# bat_connectors.net
KiCad netlist of a schematic drawn in Altium Designer
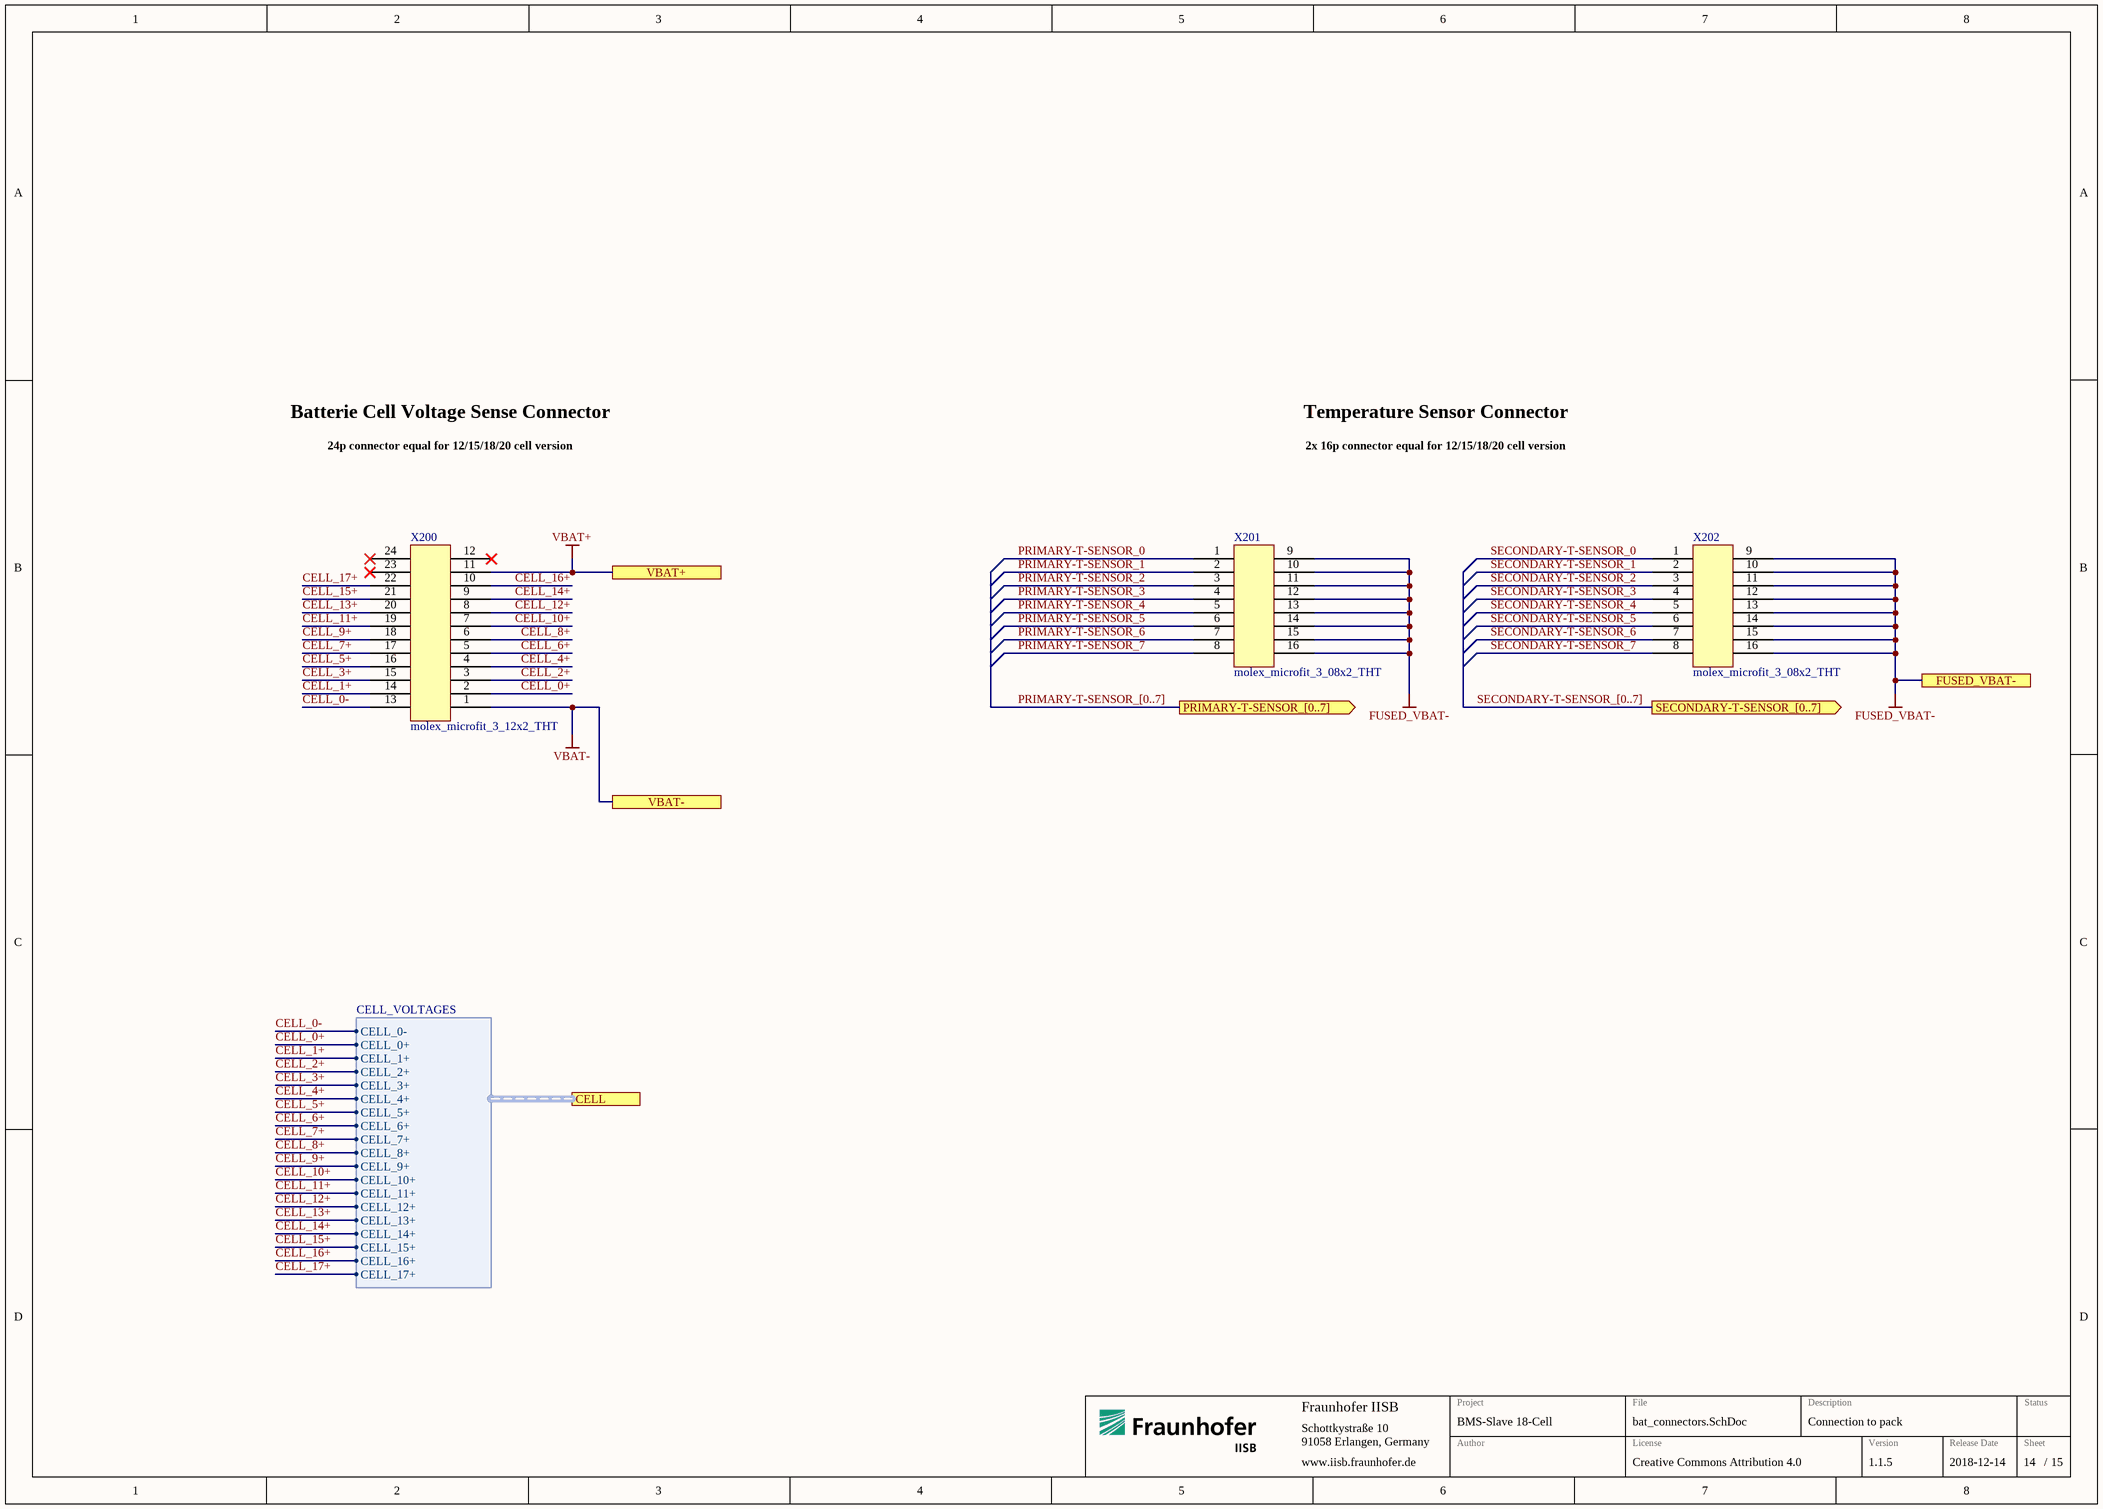
[diagram p0: bat_connectors.SchDoc]

(export (version "E")
  (design (tool "Eeschema 10.0.6"))
  (components
    (comp (ref "X200")
      (value "molex_microfit_3_12x2_THT")
      (footprint "MOLEX_MICROFIT_12x2_THT")
      (fields (field (name "MANUFACTURER") "Molex"))
      (libsource (lib "OE750") (part "X12x2"))
    )
    (comp (ref "X201")
      (value "molex_microfit_3_08x2_THT")
      (footprint "MOLEX_MICROFIT_08x2_THT")
      (fields (field (name "MANUFACTURER") "Molex"))
      (libsource (lib "OE750") (part "X8x2"))
    )
    (comp (ref "X202")
      (value "molex_microfit_3_08x2_THT")
      (footprint "MOLEX_MICROFIT_08x2_THT")
      (fields (field (name "MANUFACTURER") "Molex"))
      (libsource (lib "OE750") (part "X8x2"))
    )
  )
  (nets
    (net (code "2") (name "/CELL_0+") (class "Default") (node (ref "X200") (pin "2") (pintype "passive")))
    (net (code "3") (name "/CELL_0-") (class "Default") (node (ref "X200") (pin "13") (pintype "passive")))
    (net (code "4") (name "/CELL_1+") (class "Default") (node (ref "X200") (pin "14") (pintype "passive")))
    (net (code "5") (name "/CELL_2+") (class "Default") (node (ref "X200") (pin "3") (pintype "passive")))
    (net (code "6") (name "/CELL_3+") (class "Default") (node (ref "X200") (pin "15") (pintype "passive")))
    (net (code "7") (name "/CELL_4+") (class "Default") (node (ref "X200") (pin "4") (pintype "passive")))
    (net (code "8") (name "/CELL_5+") (class "Default") (node (ref "X200") (pin "16") (pintype "passive")))
    (net (code "9") (name "/CELL_6+") (class "Default") (node (ref "X200") (pin "5") (pintype "passive")))
    (net (code "10") (name "/CELL_7+") (class "Default") (node (ref "X200") (pin "17") (pintype "passive")))
    (net (code "11") (name "/CELL_8+") (class "Default") (node (ref "X200") (pin "6") (pintype "passive")))
    (net (code "12") (name "/CELL_9+") (class "Default") (node (ref "X200") (pin "18") (pintype "passive")))
    (net (code "13") (name "/CELL_10+") (class "Default") (node (ref "X200") (pin "7") (pintype "passive")))
    (net (code "14") (name "/CELL_11+") (class "Default") (node (ref "X200") (pin "19") (pintype "passive")))
    (net (code "15") (name "/CELL_12+") (class "Default") (node (ref "X200") (pin "8") (pintype "passive")))
    (net (code "16") (name "/CELL_13+") (class "Default") (node (ref "X200") (pin "20") (pintype "passive")))
    (net (code "17") (name "/CELL_14+") (class "Default") (node (ref "X200") (pin "9") (pintype "passive")))
    (net (code "18") (name "/CELL_15+") (class "Default") (node (ref "X200") (pin "21") (pintype "passive")))
    (net (code "19") (name "/CELL_16+") (class "Default") (node (ref "X200") (pin "10") (pintype "passive")))
    (net (code "20") (name "/CELL_17+") (class "Default") (node (ref "X200") (pin "22") (pintype "passive")))
    (net (code "21") (name "/PRIMARY-T-SENSOR_0") (class "Default")
      (node (ref "X201") (pin "1") (pintype "passive"))
    )
    (net (code "22") (name "/PRIMARY-T-SENSOR_1") (class "Default")
      (node (ref "X201") (pin "2") (pintype "passive"))
    )
    (net (code "23") (name "/PRIMARY-T-SENSOR_2") (class "Default")
      (node (ref "X201") (pin "3") (pintype "passive"))
    )
    (net (code "24") (name "/PRIMARY-T-SENSOR_3") (class "Default")
      (node (ref "X201") (pin "4") (pintype "passive"))
    )
    (net (code "25") (name "/PRIMARY-T-SENSOR_4") (class "Default")
      (node (ref "X201") (pin "5") (pintype "passive"))
    )
    (net (code "26") (name "/PRIMARY-T-SENSOR_5") (class "Default")
      (node (ref "X201") (pin "6") (pintype "passive"))
    )
    (net (code "27") (name "/PRIMARY-T-SENSOR_6") (class "Default")
      (node (ref "X201") (pin "7") (pintype "passive"))
    )
    (net (code "28") (name "/PRIMARY-T-SENSOR_7") (class "Default")
      (node (ref "X201") (pin "8") (pintype "passive"))
    )
    (net (code "30") (name "/SECONDARY-T-SENSOR_0") (class "Default")
      (node (ref "X202") (pin "1") (pintype "passive"))
    )
    (net (code "31") (name "/SECONDARY-T-SENSOR_1") (class "Default")
      (node (ref "X202") (pin "2") (pintype "passive"))
    )
    (net (code "32") (name "/SECONDARY-T-SENSOR_2") (class "Default")
      (node (ref "X202") (pin "3") (pintype "passive"))
    )
    (net (code "33") (name "/SECONDARY-T-SENSOR_3") (class "Default")
      (node (ref "X202") (pin "4") (pintype "passive"))
    )
    (net (code "34") (name "/SECONDARY-T-SENSOR_4") (class "Default")
      (node (ref "X202") (pin "5") (pintype "passive"))
    )
    (net (code "35") (name "/SECONDARY-T-SENSOR_5") (class "Default")
      (node (ref "X202") (pin "6") (pintype "passive"))
    )
    (net (code "36") (name "/SECONDARY-T-SENSOR_6") (class "Default")
      (node (ref "X202") (pin "7") (pintype "passive"))
    )
    (net (code "37") (name "/SECONDARY-T-SENSOR_7") (class "Default")
      (node (ref "X202") (pin "8") (pintype "passive"))
    )
    (net (code "40") (name "FUSED_VBAT-") (class "Default")
      (node (ref "X201") (pin "10") (pintype "passive"))
      (node (ref "X201") (pin "11") (pintype "passive"))
      (node (ref "X201") (pin "12") (pintype "passive"))
      (node (ref "X201") (pin "13") (pintype "passive"))
      (node (ref "X201") (pin "14") (pintype "passive"))
      (node (ref "X201") (pin "15") (pintype "passive"))
      (node (ref "X201") (pin "16") (pintype "passive"))
      (node (ref "X201") (pin "9") (pintype "passive"))
      (node (ref "X202") (pin "10") (pintype "passive"))
      (node (ref "X202") (pin "11") (pintype "passive"))
      (node (ref "X202") (pin "12") (pintype "passive"))
      (node (ref "X202") (pin "13") (pintype "passive"))
      (node (ref "X202") (pin "14") (pintype "passive"))
      (node (ref "X202") (pin "15") (pintype "passive"))
      (node (ref "X202") (pin "16") (pintype "passive"))
      (node (ref "X202") (pin "9") (pintype "passive"))
    )
    (net (code "41") (name "VBAT+") (class "Default") (node (ref "X200") (pin "11") (pintype "passive")))
    (net (code "42") (name "VBAT-") (class "Default") (node (ref "X200") (pin "1") (pintype "passive")))
    (net (code "43") (name "unconnected-(X200-Pad12)") (class "Default")
      (node (ref "X200") (pin "12") (pintype "passive+no_connect"))
    )
    (net (code "44") (name "unconnected-(X200-Pad23)") (class "Default")
      (node (ref "X200") (pin "23") (pintype "passive+no_connect"))
    )
    (net (code "45") (name "unconnected-(X200-Pad24)") (class "Default")
      (node (ref "X200") (pin "24") (pintype "passive+no_connect"))
    )
  )
)
